# Fuse.net
KiCad netlist of a schematic drawn in Altium Designer
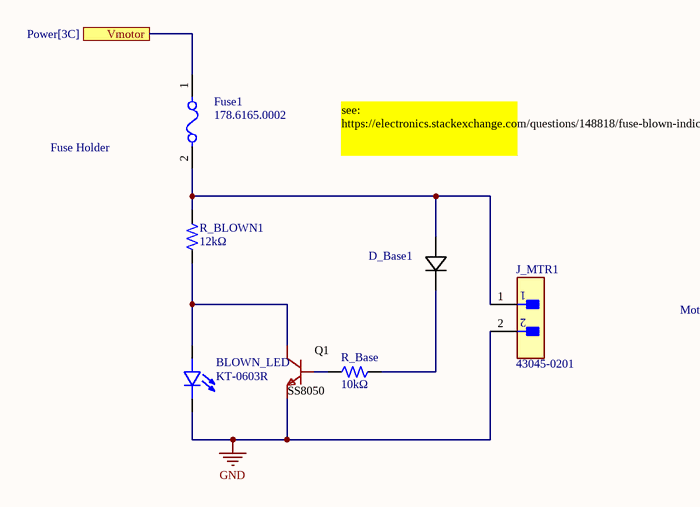
[diagram p0: Fuse.SchDoc]

(export (version "E")
  (design (tool "Eeschema 10.0.6"))
  (components
    (comp (ref "BLOWN_LED")
      (value "KT-0603R")
      (footprint "LED_KT-0603R")
      (description "Red 0603 Light Emitting Diodes")
      (fields (field (name "MF") "Hubei KENTO Elec"))
      (libsource (lib "KT-0603R") (part "KT-0603R"))
    )
    (comp (ref "D_Base1")
      (value "Diode")
      (footprint "M7:M7_MDD")
      (description "1A Independent Type 1kV 1.1V@1A SMA(DO-214AC) Diodes - General Purpose ROHS")
      (libsource (lib "M7") (part "M7"))
    )
    (comp (ref "Fuse1")
      (value "178.6165.0002")
      (footprint "FP-178_6165-MFG")
      (description "FUSE HOLDER BLADE 80V PCB")
      (fields
        (field (name "MANUFACTURER") "Littelfuse")
        (field (name "OCTOPART") "https://octopart.com/178.6165.0002-littelfuse-13138759")
      )
      (libsource (lib "Altium Content Vault") (part "5bcf9b9f640e542cf0359d10258e979"))
    )
    (comp (ref "J_MTR1")
      (value "43045-0201")
      (footprint "FP-43045-0201-MFG")
      (description "CONN HEADER R/A 2POS")
      (libsource (lib "Altium Content Vault") (part "3bc925449376181038e59eaffc5286c"))
    )
    (comp (ref "Q1")
      (value "SS8050")
      (footprint "SOT-23-3_L2.9-W1.3-P1.90-LS2.4-BR")
      (description "BJT NPN")
      (fields
        (field (name "MANUFACTURER") "CJ(江苏长电/长晶)")
        (field (name "MANUFACTURER PART") "SS8050(RANGE:200-350)")
      )
      (libsource (lib "SS8050_C21501_SS8050_C2150") (part "SS8050(RANGE{colon}200-350)_C2150"))
    )
    (comp (ref "R_Base")
      (value "0603WAF1002T5E")
      (footprint "RES-0603")
      (description "Resistor, 10kΩ, ±1%, 100mW, 75V, ±100ppm/℃, -55℃~+155℃, SMD 0603")
      (fields
        (field (name "MANUFACTURER") "Uniroyal")
        (field (name "JLCPCB PART NUMBER") "C25804")
        (field (name "RESISTANCE") "10kΩ")
      )
      (libsource (lib "jlcpcb_2024_10_resistors_basic") (part "0603WAF1002T5E"))
    )
    (comp (ref "R_BLOWN1")
      (value "0402WGF1202TCE")
      (footprint "RES-0402")
      (description "Resistor, 12kΩ, ±1%, 62.5mW, 50V, ±100ppm/℃, -55℃~+155℃, SMD 0402")
      (fields
        (field (name "MANUFACTURER") "Uniroyal")
        (field (name "JLCPCB PART NUMBER") "C25752")
        (field (name "RESISTANCE") "12kΩ")
      )
      (libsource (lib "jlcpcb_2024_10_resistors_basic") (part "0402WGF1202TCE"))
    )
  )
  (nets
    (net (code "1") (name "/Vmotor") (class "Default")
      (node (ref "Fuse1") (pin "1") (pinfunction "1_1") (pintype "passive"))
    )
    (net (code "2") (name "GND") (class "Default")
      (node (ref "BLOWN_LED") (pin "C") (pinfunction "C_C") (pintype "passive"))
      (node (ref "J_MTR1") (pin "2") (pinfunction "2_2") (pintype "passive"))
      (node (ref "Q1") (pin "2") (pinfunction "E_2") (pintype "passive"))
    )
    (net (code "3") (name "Net-(D_Base1-ANODE)") (class "Default")
      (node (ref "D_Base1") (pin "2") (pinfunction "ANODE_2") (pintype "passive"))
      (node (ref "Fuse1") (pin "2") (pinfunction "2_2") (pintype "passive"))
      (node (ref "J_MTR1") (pin "1") (pinfunction "1_1") (pintype "passive"))
      (node (ref "R_BLOWN1") (pin "2") (pinfunction "2_2") (pintype "passive"))
    )
    (net (code "4") (name "Net-(D_Base1-CATHODE)") (class "Default")
      (node (ref "D_Base1") (pin "1") (pinfunction "CATHODE_1") (pintype "passive"))
      (node (ref "R_Base") (pin "2") (pinfunction "2_2") (pintype "passive"))
    )
    (net (code "5") (name "Net-(Q1-B)") (class "Default")
      (node (ref "Q1") (pin "1") (pinfunction "B_1") (pintype "passive"))
      (node (ref "R_Base") (pin "1") (pinfunction "1_1") (pintype "passive"))
    )
    (net (code "6") (name "Net-(Q1-C)") (class "Default")
      (node (ref "BLOWN_LED") (pin "A") (pinfunction "A_A") (pintype "passive"))
      (node (ref "Q1") (pin "3") (pinfunction "C_3") (pintype "passive"))
      (node (ref "R_BLOWN1") (pin "1") (pinfunction "1_1") (pintype "passive"))
    )
  )
)
